# Batterie.net
KiCad netlist of a schematic drawn in EAGLE
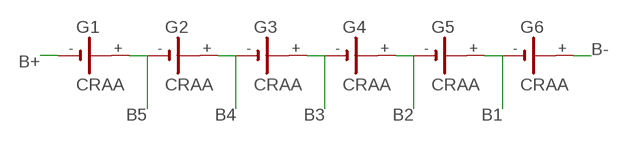
[diagram p0: schematic, sheet 1]

(export (version "E")
  (design (tool "Eeschema 10.0.6"))
  (components
    (comp (ref "G1")
      (value "CRAA")
      (footprint "eagle-import:CRAA")
      (libsource (lib "eagle-import") (part "CRAA"))
    )
    (comp (ref "G2")
      (value "CRAA")
      (footprint "eagle-import:CRAA")
      (libsource (lib "eagle-import") (part "CRAA"))
    )
    (comp (ref "G3")
      (value "CRAA")
      (footprint "eagle-import:CRAA")
      (libsource (lib "eagle-import") (part "CRAA"))
    )
    (comp (ref "G4")
      (value "CRAA")
      (footprint "eagle-import:CRAA")
      (libsource (lib "eagle-import") (part "CRAA"))
    )
    (comp (ref "G5")
      (value "CRAA")
      (footprint "eagle-import:CRAA")
      (libsource (lib "eagle-import") (part "CRAA"))
    )
    (comp (ref "G6")
      (value "CRAA")
      (footprint "eagle-import:CRAA")
      (libsource (lib "eagle-import") (part "CRAA"))
    )
  )
  (nets
    (net (code "1") (name "/B+") (class "Default")
      (node (ref "G1") (pin "-") (pinfunction "-_-") (pintype "passive"))
    )
    (net (code "2") (name "/B-") (class "Default")
      (node (ref "G6") (pin "+") (pinfunction "+_+") (pintype "passive"))
    )
    (net (code "3") (name "/B1") (class "Default")
      (node (ref "G5") (pin "+") (pinfunction "+_+") (pintype "passive"))
      (node (ref "G6") (pin "-") (pinfunction "-_-") (pintype "passive"))
    )
    (net (code "4") (name "/B2") (class "Default")
      (node (ref "G4") (pin "+") (pinfunction "+_+") (pintype "passive"))
      (node (ref "G5") (pin "-") (pinfunction "-_-") (pintype "passive"))
    )
    (net (code "5") (name "/B3") (class "Default")
      (node (ref "G3") (pin "+") (pinfunction "+_+") (pintype "passive"))
      (node (ref "G4") (pin "-") (pinfunction "-_-") (pintype "passive"))
    )
    (net (code "6") (name "/B4") (class "Default")
      (node (ref "G2") (pin "+") (pinfunction "+_+") (pintype "passive"))
      (node (ref "G3") (pin "-") (pinfunction "-_-") (pintype "passive"))
    )
    (net (code "7") (name "/B5") (class "Default")
      (node (ref "G1") (pin "+") (pinfunction "+_+") (pintype "passive"))
      (node (ref "G2") (pin "-") (pinfunction "-_-") (pintype "passive"))
    )
    (net (code "8") (name "unconnected-(G1-+-Pad+@1)") (class "Default")
      (node (ref "G1") (pin "+@1") (pinfunction "+_+@1") (pintype "passive"))
    )
    (net (code "9") (name "unconnected-(G2-+-Pad+@1)") (class "Default")
      (node (ref "G2") (pin "+@1") (pinfunction "+_+@1") (pintype "passive"))
    )
    (net (code "10") (name "unconnected-(G3-+-Pad+@1)") (class "Default")
      (node (ref "G3") (pin "+@1") (pinfunction "+_+@1") (pintype "passive"))
    )
    (net (code "11") (name "unconnected-(G4-+-Pad+@1)") (class "Default")
      (node (ref "G4") (pin "+@1") (pinfunction "+_+@1") (pintype "passive"))
    )
    (net (code "12") (name "unconnected-(G5-+-Pad+@1)") (class "Default")
      (node (ref "G5") (pin "+@1") (pinfunction "+_+@1") (pintype "passive"))
    )
    (net (code "13") (name "unconnected-(G6-+-Pad+@1)") (class "Default")
      (node (ref "G6") (pin "+@1") (pinfunction "+_+@1") (pintype "passive"))
    )
  )
)
